# 4ch_relay.net
KiCad netlist of a schematic drawn in EAGLE
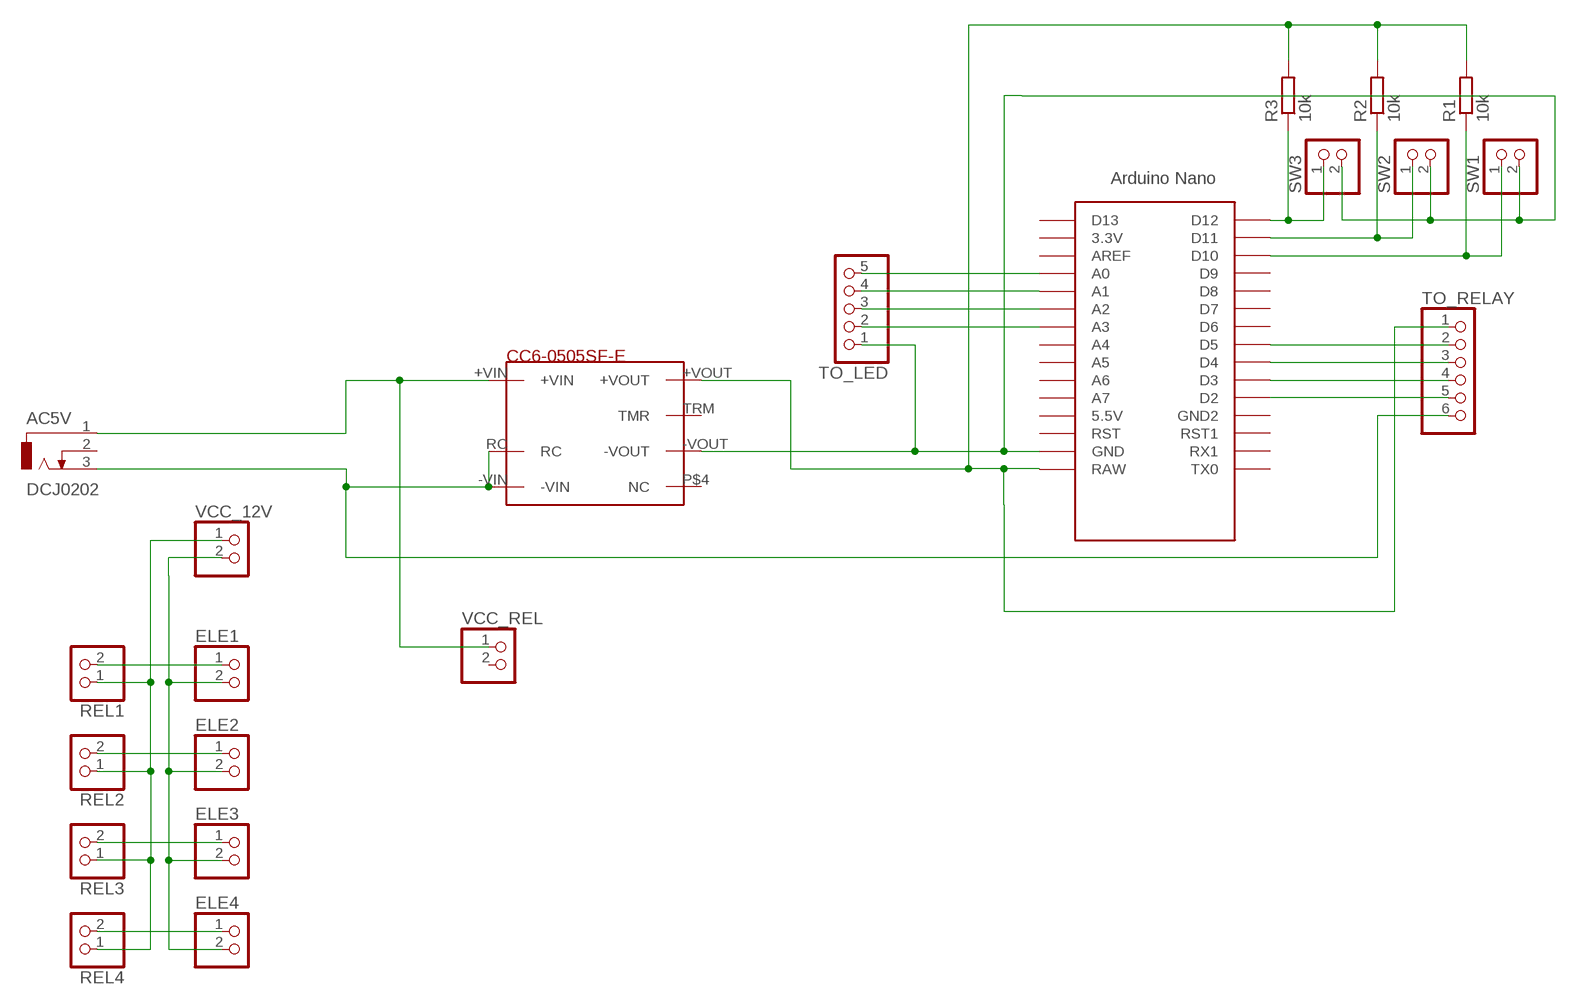
[diagram p0: schematic, sheet 1]

(export (version "E")
  (design (tool "Eeschema 10.0.6"))
  (components
    (comp (ref "AC5V")
      (value "DCJ0202")
      (footprint "eagle-import:DCJ0202")
      (libsource (lib "eagle-import") (part "DCJ0202"))
    )
    (comp (ref "DC-DC1")
      (value "DC-DC-CONVERTER")
      (footprint "eagle-import:DC_DC_CONVERTER")
      (libsource (lib "eagle-import") (part "DC-DC-CONVERTER"))
    )
    (comp (ref "ELE1")
      (value "PINHD-1X2")
      (footprint "eagle-import:1X02")
      (libsource (lib "eagle-import") (part "PINHD-1X2"))
    )
    (comp (ref "ELE2")
      (value "PINHD-1X2")
      (footprint "eagle-import:1X02")
      (libsource (lib "eagle-import") (part "PINHD-1X2"))
    )
    (comp (ref "ELE3")
      (value "PINHD-1X2")
      (footprint "eagle-import:1X02")
      (libsource (lib "eagle-import") (part "PINHD-1X2"))
    )
    (comp (ref "ELE4")
      (value "PINHD-1X2")
      (footprint "eagle-import:1X02")
      (libsource (lib "eagle-import") (part "PINHD-1X2"))
    )
    (comp (ref "R1")
      (value "10k")
      (footprint "eagle-import:0207_10")
      (libsource (lib "eagle-import") (part "R-EU_0207/10"))
    )
    (comp (ref "R2")
      (value "10k")
      (footprint "eagle-import:0207_10")
      (libsource (lib "eagle-import") (part "R-EU_0207/10"))
    )
    (comp (ref "R3")
      (value "10k")
      (footprint "eagle-import:0207_10")
      (libsource (lib "eagle-import") (part "R-EU_0207/10"))
    )
    (comp (ref "REL1")
      (value "PINHD-1X2")
      (footprint "eagle-import:1X02")
      (libsource (lib "eagle-import") (part "PINHD-1X2"))
    )
    (comp (ref "REL2")
      (value "PINHD-1X2")
      (footprint "eagle-import:1X02")
      (libsource (lib "eagle-import") (part "PINHD-1X2"))
    )
    (comp (ref "REL3")
      (value "PINHD-1X2")
      (footprint "eagle-import:1X02")
      (libsource (lib "eagle-import") (part "PINHD-1X2"))
    )
    (comp (ref "REL4")
      (value "PINHD-1X2")
      (footprint "eagle-import:1X02")
      (libsource (lib "eagle-import") (part "PINHD-1X2"))
    )
    (comp (ref "SW1")
      (value "PINHD-1X2")
      (footprint "eagle-import:1X02")
      (libsource (lib "eagle-import") (part "PINHD-1X2"))
    )
    (comp (ref "SW2")
      (value "PINHD-1X2")
      (footprint "eagle-import:1X02")
      (libsource (lib "eagle-import") (part "PINHD-1X2"))
    )
    (comp (ref "SW3")
      (value "PINHD-1X2")
      (footprint "eagle-import:1X02")
      (libsource (lib "eagle-import") (part "PINHD-1X2"))
    )
    (comp (ref "TO_LED")
      (value "PINHD-1X5")
      (footprint "eagle-import:1X05")
      (libsource (lib "eagle-import") (part "PINHD-1X5"))
    )
    (comp (ref "TO_RELAY")
      (value "PINHD-1X6")
      (footprint "eagle-import:1X06")
      (libsource (lib "eagle-import") (part "PINHD-1X6"))
    )
    (comp (ref "U$1")
      (value "NANO")
      (footprint "eagle-import:NANO")
      (libsource (lib "eagle-import") (part "NANO"))
    )
    (comp (ref "VCC_12V")
      (value "PINHD-1X2")
      (footprint "eagle-import:1X02")
      (libsource (lib "eagle-import") (part "PINHD-1X2"))
    )
    (comp (ref "VCC_REL")
      (value "PINHD-1X2")
      (footprint "eagle-import:1X02")
      (libsource (lib "eagle-import") (part "PINHD-1X2"))
    )
  )
  (nets
    (net (code "1") (name "Net-(AC5V-Pad1)") (class "Default")
      (node (ref "AC5V") (pin "1") (pinfunction "1_1") (pintype "passive"))
      (node (ref "DC-DC1") (pin "+VIN") (pinfunction "+VIN_+VIN") (pintype "bidirectional"))
      (node (ref "VCC_REL") (pin "1") (pinfunction "1_1") (pintype "passive"))
    )
    (net (code "2") (name "Net-(AC5V-Pad3)") (class "Default")
      (node (ref "AC5V") (pin "3") (pinfunction "3_3") (pintype "passive"))
      (node (ref "DC-DC1") (pin "-VIN") (pinfunction "-VIN_-VIN") (pintype "bidirectional"))
      (node (ref "DC-DC1") (pin "RC") (pinfunction "RC_RC") (pintype "bidirectional"))
      (node (ref "TO_RELAY") (pin "6") (pinfunction "6_6") (pintype "passive"))
    )
    (net (code "3") (name "Net-(DC-DC1-Pad+VOUT)") (class "Default")
      (node (ref "DC-DC1") (pin "+VOUT") (pinfunction "+VOUT_+VOUT") (pintype "bidirectional"))
      (node (ref "R1") (pin "2") (pinfunction "2_2") (pintype "passive"))
      (node (ref "R2") (pin "2") (pinfunction "2_2") (pintype "passive"))
      (node (ref "R3") (pin "2") (pinfunction "2_2") (pintype "passive"))
      (node (ref "TO_RELAY") (pin "1") (pinfunction "1_1") (pintype "passive"))
      (node (ref "U$1") (pin "RAW") (pinfunction "RAW_RAW") (pintype "bidirectional"))
    )
    (net (code "4") (name "Net-(DC-DC1-Pad-VOUT)") (class "Default")
      (node (ref "DC-DC1") (pin "-VOUT") (pinfunction "-VOUT_-VOUT") (pintype "bidirectional"))
      (node (ref "SW1") (pin "2") (pinfunction "2_2") (pintype "passive"))
      (node (ref "SW2") (pin "2") (pinfunction "2_2") (pintype "passive"))
      (node (ref "SW3") (pin "2") (pinfunction "2_2") (pintype "passive"))
      (node (ref "TO_LED") (pin "1") (pinfunction "1_1") (pintype "passive"))
      (node (ref "U$1") (pin "GND") (pinfunction "GND_GND") (pintype "bidirectional"))
    )
    (net (code "5") (name "Net-(ELE1-Pad1)") (class "Default")
      (node (ref "ELE1") (pin "1") (pinfunction "1_1") (pintype "passive"))
      (node (ref "REL1") (pin "2") (pinfunction "2_2") (pintype "passive"))
    )
    (net (code "6") (name "Net-(ELE1-Pad2)") (class "Default")
      (node (ref "ELE1") (pin "2") (pinfunction "2_2") (pintype "passive"))
      (node (ref "ELE2") (pin "2") (pinfunction "2_2") (pintype "passive"))
      (node (ref "ELE3") (pin "2") (pinfunction "2_2") (pintype "passive"))
      (node (ref "ELE4") (pin "2") (pinfunction "2_2") (pintype "passive"))
      (node (ref "VCC_12V") (pin "2") (pinfunction "2_2") (pintype "passive"))
    )
    (net (code "7") (name "Net-(ELE2-Pad1)") (class "Default")
      (node (ref "ELE2") (pin "1") (pinfunction "1_1") (pintype "passive"))
      (node (ref "REL2") (pin "2") (pinfunction "2_2") (pintype "passive"))
    )
    (net (code "8") (name "Net-(ELE3-Pad1)") (class "Default")
      (node (ref "ELE3") (pin "1") (pinfunction "1_1") (pintype "passive"))
      (node (ref "REL3") (pin "2") (pinfunction "2_2") (pintype "passive"))
    )
    (net (code "9") (name "Net-(ELE4-Pad1)") (class "Default")
      (node (ref "ELE4") (pin "1") (pinfunction "1_1") (pintype "passive"))
      (node (ref "REL4") (pin "2") (pinfunction "2_2") (pintype "passive"))
    )
    (net (code "10") (name "Net-(R1-Pad1)") (class "Default")
      (node (ref "R1") (pin "1") (pinfunction "1_1") (pintype "passive"))
      (node (ref "SW1") (pin "1") (pinfunction "1_1") (pintype "passive"))
      (node (ref "U$1") (pin "D10") (pinfunction "D10_D10") (pintype "bidirectional"))
    )
    (net (code "11") (name "Net-(R2-Pad1)") (class "Default")
      (node (ref "R2") (pin "1") (pinfunction "1_1") (pintype "passive"))
      (node (ref "SW2") (pin "1") (pinfunction "1_1") (pintype "passive"))
      (node (ref "U$1") (pin "D11") (pinfunction "D11_D11") (pintype "bidirectional"))
    )
    (net (code "12") (name "Net-(R3-Pad1)") (class "Default")
      (node (ref "R3") (pin "1") (pinfunction "1_1") (pintype "passive"))
      (node (ref "SW3") (pin "1") (pinfunction "1_1") (pintype "passive"))
      (node (ref "U$1") (pin "D12") (pinfunction "D12_D12") (pintype "bidirectional"))
    )
    (net (code "13") (name "Net-(REL1-Pad1)") (class "Default")
      (node (ref "REL1") (pin "1") (pinfunction "1_1") (pintype "passive"))
      (node (ref "REL2") (pin "1") (pinfunction "1_1") (pintype "passive"))
      (node (ref "REL3") (pin "1") (pinfunction "1_1") (pintype "passive"))
      (node (ref "REL4") (pin "1") (pinfunction "1_1") (pintype "passive"))
      (node (ref "VCC_12V") (pin "1") (pinfunction "1_1") (pintype "passive"))
    )
    (net (code "14") (name "Net-(TO_LED-Pad2)") (class "Default")
      (node (ref "TO_LED") (pin "2") (pinfunction "2_2") (pintype "passive"))
      (node (ref "U$1") (pin "A3") (pinfunction "A3_A3") (pintype "bidirectional"))
    )
    (net (code "15") (name "Net-(TO_LED-Pad3)") (class "Default")
      (node (ref "TO_LED") (pin "3") (pinfunction "3_3") (pintype "passive"))
      (node (ref "U$1") (pin "A2") (pinfunction "A2_A2") (pintype "bidirectional"))
    )
    (net (code "16") (name "Net-(TO_LED-Pad4)") (class "Default")
      (node (ref "TO_LED") (pin "4") (pinfunction "4_4") (pintype "passive"))
      (node (ref "U$1") (pin "A1") (pinfunction "A1_A1") (pintype "bidirectional"))
    )
    (net (code "17") (name "Net-(TO_LED-Pad5)") (class "Default")
      (node (ref "TO_LED") (pin "5") (pinfunction "5_5") (pintype "passive"))
      (node (ref "U$1") (pin "A0") (pinfunction "A0_A0") (pintype "bidirectional"))
    )
    (net (code "18") (name "Net-(TO_RELAY-Pad2)") (class "Default")
      (node (ref "TO_RELAY") (pin "2") (pinfunction "2_2") (pintype "passive"))
      (node (ref "U$1") (pin "D5") (pinfunction "D5_D5") (pintype "bidirectional"))
    )
    (net (code "19") (name "Net-(TO_RELAY-Pad3)") (class "Default")
      (node (ref "TO_RELAY") (pin "3") (pinfunction "3_3") (pintype "passive"))
      (node (ref "U$1") (pin "D4") (pinfunction "D4_D4") (pintype "bidirectional"))
    )
    (net (code "20") (name "Net-(TO_RELAY-Pad4)") (class "Default")
      (node (ref "TO_RELAY") (pin "4") (pinfunction "4_4") (pintype "passive"))
      (node (ref "U$1") (pin "D3") (pinfunction "D3_D3") (pintype "bidirectional"))
    )
    (net (code "21") (name "Net-(TO_RELAY-Pad5)") (class "Default")
      (node (ref "TO_RELAY") (pin "5") (pinfunction "5_5") (pintype "passive"))
      (node (ref "U$1") (pin "D2") (pinfunction "D2_D2") (pintype "bidirectional"))
    )
    (net (code "22") (name "unconnected-(AC5V-Pad2)") (class "Default")
      (node (ref "AC5V") (pin "2") (pinfunction "2_2") (pintype "passive"))
    )
    (net (code "23") (name "unconnected-(DC-DC1-NC-PadP$4)") (class "Default")
      (node (ref "DC-DC1") (pin "P$4") (pinfunction "NC_P$4") (pintype "bidirectional"))
    )
    (net (code "24") (name "unconnected-(DC-DC1-TMR-PadTRM)") (class "Default")
      (node (ref "DC-DC1") (pin "TRM") (pinfunction "TMR_TRM") (pintype "bidirectional"))
    )
    (net (code "25") (name "unconnected-(U$1-5.5V-Pad5V)") (class "Default")
      (node (ref "U$1") (pin "5V") (pinfunction "5.5V_5V") (pintype "bidirectional"))
    )
    (net (code "26") (name "unconnected-(U$1-GND2-PadGND1)") (class "Default")
      (node (ref "U$1") (pin "GND1") (pinfunction "GND2_GND1") (pintype "bidirectional"))
    )
    (net (code "27") (name "unconnected-(U$1-Pad3.3V)") (class "Default")
      (node (ref "U$1") (pin "3.3V") (pinfunction "3.3V_3.3V") (pintype "bidirectional"))
    )
    (net (code "28") (name "unconnected-(U$1-PadA4)") (class "Default")
      (node (ref "U$1") (pin "A4") (pinfunction "A4_A4") (pintype "bidirectional"))
    )
    (net (code "29") (name "unconnected-(U$1-PadA5)") (class "Default")
      (node (ref "U$1") (pin "A5") (pinfunction "A5_A5") (pintype "bidirectional"))
    )
    (net (code "30") (name "unconnected-(U$1-PadA6)") (class "Default")
      (node (ref "U$1") (pin "A6") (pinfunction "A6_A6") (pintype "bidirectional"))
    )
    (net (code "31") (name "unconnected-(U$1-PadA7)") (class "Default")
      (node (ref "U$1") (pin "A7") (pinfunction "A7_A7") (pintype "bidirectional"))
    )
    (net (code "32") (name "unconnected-(U$1-PadAREF)") (class "Default")
      (node (ref "U$1") (pin "AREF") (pinfunction "AREF_AREF") (pintype "bidirectional"))
    )
    (net (code "33") (name "unconnected-(U$1-PadD6)") (class "Default")
      (node (ref "U$1") (pin "D6") (pinfunction "D6_D6") (pintype "bidirectional"))
    )
    (net (code "34") (name "unconnected-(U$1-PadD7)") (class "Default")
      (node (ref "U$1") (pin "D7") (pinfunction "D7_D7") (pintype "bidirectional"))
    )
    (net (code "35") (name "unconnected-(U$1-PadD8)") (class "Default")
      (node (ref "U$1") (pin "D8") (pinfunction "D8_D8") (pintype "bidirectional"))
    )
    (net (code "36") (name "unconnected-(U$1-PadD9)") (class "Default")
      (node (ref "U$1") (pin "D9") (pinfunction "D9_D9") (pintype "bidirectional"))
    )
    (net (code "37") (name "unconnected-(U$1-PadD13)") (class "Default")
      (node (ref "U$1") (pin "D13") (pinfunction "D13_D13") (pintype "bidirectional"))
    )
    (net (code "38") (name "unconnected-(U$1-PadICSP1)") (class "Default")
      (node (ref "U$1") (pin "ICSP1") (pinfunction "ICSP1_ICSP1") (pintype "bidirectional"))
    )
    (net (code "39") (name "unconnected-(U$1-PadICSP2)") (class "Default")
      (node (ref "U$1") (pin "ICSP2") (pinfunction "ICSP2_ICSP2") (pintype "bidirectional"))
    )
    (net (code "40") (name "unconnected-(U$1-PadICSP3)") (class "Default")
      (node (ref "U$1") (pin "ICSP3") (pinfunction "ICSP3_ICSP3") (pintype "bidirectional"))
    )
    (net (code "41") (name "unconnected-(U$1-PadICSP4)") (class "Default")
      (node (ref "U$1") (pin "ICSP4") (pinfunction "ICSP4_ICSP4") (pintype "bidirectional"))
    )
    (net (code "42") (name "unconnected-(U$1-PadICSP5)") (class "Default")
      (node (ref "U$1") (pin "ICSP5") (pinfunction "ICSP5_ICSP5") (pintype "bidirectional"))
    )
    (net (code "43") (name "unconnected-(U$1-PadICSP6)") (class "Default")
      (node (ref "U$1") (pin "ICSP6") (pinfunction "ICSP6_ICSP6") (pintype "bidirectional"))
    )
    (net (code "44") (name "unconnected-(U$1-PadRST)") (class "Default")
      (node (ref "U$1") (pin "RST") (pinfunction "RST_RST") (pintype "bidirectional"))
    )
    (net (code "45") (name "unconnected-(U$1-PadRST1)") (class "Default")
      (node (ref "U$1") (pin "RST1") (pinfunction "RST1_RST1") (pintype "bidirectional"))
    )
    (net (code "46") (name "unconnected-(U$1-PadRX1)") (class "Default")
      (node (ref "U$1") (pin "RX1") (pinfunction "RX1_RX1") (pintype "bidirectional"))
    )
    (net (code "47") (name "unconnected-(U$1-PadTX0)") (class "Default")
      (node (ref "U$1") (pin "TX0") (pinfunction "TX0_TX0") (pintype "bidirectional"))
    )
    (net (code "48") (name "unconnected-(VCC_REL-Pad2)") (class "Default")
      (node (ref "VCC_REL") (pin "2") (pinfunction "2_2") (pintype "passive"))
    )
  )
)
